# k26_baseboard_reset.net
KiCad netlist of a schematic drawn in Altium Designer
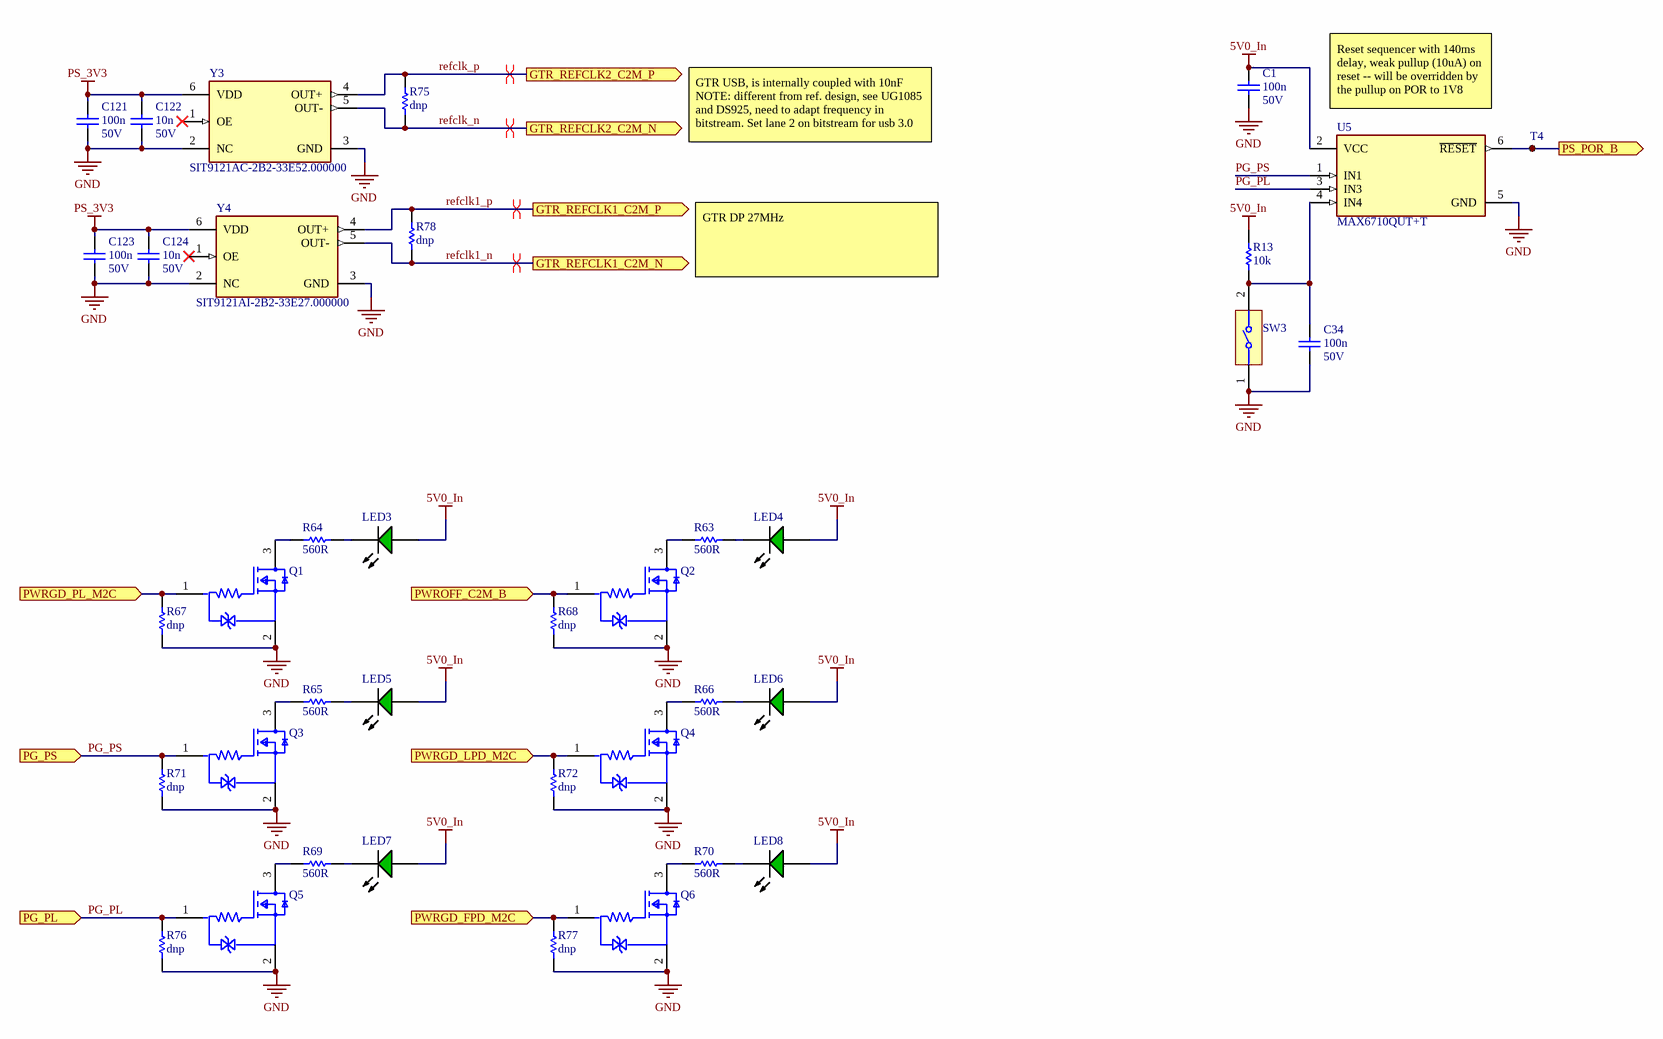
[diagram p0: k26_baseboard_reset.SchDoc]

(export (version "E")
  (design (tool "Eeschema 10.0.6"))
  (components
    (comp (ref "C1")
      (value "100n")
      (footprint "k26_FPGA_drone_baseboard:CAPC0402")
      (fields
        (field (name "MANUFACTURER") "Yageo")
        (field (name "MANUFACTURER PART NUMBER") "CC0402KRX5R9BB104")
        (field (name "RATED DC VOLTAGE (URDC)") "50V")
      )
      (libsource (lib "k26_FPGA_drone_baseboard") (part "cap0402"))
    )
    (comp (ref "C34")
      (value "100n")
      (footprint "k26_FPGA_drone_baseboard:CAPC0402")
      (fields
        (field (name "MANUFACTURER") "Yageo")
        (field (name "MANUFACTURER PART NUMBER") "CC0402KRX5R9BB104")
        (field (name "RATED DC VOLTAGE (URDC)") "50V")
      )
      (libsource (lib "k26_FPGA_drone_baseboard") (part "cap0402"))
    )
    (comp (ref "C121")
      (value "100n")
      (footprint "k26_FPGA_drone_baseboard:CAPC0402")
      (fields
        (field (name "MANUFACTURER") "Yageo")
        (field (name "MANUFACTURER PART NUMBER") "CC0402KRX5R9BB104")
        (field (name "RATED DC VOLTAGE (URDC)") "50V")
      )
      (libsource (lib "k26_FPGA_drone_baseboard") (part "cap0402"))
    )
    (comp (ref "C122")
      (value "10n")
      (footprint "k26_FPGA_drone_baseboard:CAPC0402")
      (fields
        (field (name "MANUFACTURER") "Samsung")
        (field (name "MANUFACTURER PART NUMBER") "CL05B103KB5NNNC")
        (field (name "RATED DC VOLTAGE (URDC)") "50V")
      )
      (libsource (lib "k26_FPGA_drone_baseboard") (part "cap0402"))
    )
    (comp (ref "C123")
      (value "100n")
      (footprint "k26_FPGA_drone_baseboard:CAPC0402")
      (fields
        (field (name "MANUFACTURER") "Yageo")
        (field (name "MANUFACTURER PART NUMBER") "CC0402KRX5R9BB104")
        (field (name "RATED DC VOLTAGE (URDC)") "50V")
      )
      (libsource (lib "k26_FPGA_drone_baseboard") (part "cap0402"))
    )
    (comp (ref "C124")
      (value "10n")
      (footprint "k26_FPGA_drone_baseboard:CAPC0402")
      (fields
        (field (name "MANUFACTURER") "Samsung")
        (field (name "MANUFACTURER PART NUMBER") "CL05B103KB5NNNC")
        (field (name "RATED DC VOLTAGE (URDC)") "50V")
      )
      (libsource (lib "k26_FPGA_drone_baseboard") (part "cap0402"))
    )
    (comp (ref "LED3")
      (value "LNJ347W83RA")
      (footprint "LED0402(1005)_L")
      (description "Green 572nm LED Indication - Discrete 1.95V 0402 (1005 Metric)")
      (fields (field (name "MANUFACTURER") "Panasonic SSG"))
      (libsource (lib "k26_FPGA_drone_baseboard") (part "CMP-00397-1"))
    )
    (comp (ref "LED4")
      (value "LNJ347W83RA")
      (footprint "LED0402(1005)_L")
      (description "Green 572nm LED Indication - Discrete 1.95V 0402 (1005 Metric)")
      (fields (field (name "MANUFACTURER") "Panasonic SSG"))
      (libsource (lib "k26_FPGA_drone_baseboard") (part "CMP-00397-1"))
    )
    (comp (ref "LED5")
      (value "LNJ347W83RA")
      (footprint "LED0402(1005)_L")
      (description "Green 572nm LED Indication - Discrete 1.95V 0402 (1005 Metric)")
      (fields (field (name "MANUFACTURER") "Panasonic SSG"))
      (libsource (lib "k26_FPGA_drone_baseboard") (part "CMP-00397-1"))
    )
    (comp (ref "LED6")
      (value "LNJ347W83RA")
      (footprint "LED0402(1005)_L")
      (description "Green 572nm LED Indication - Discrete 1.95V 0402 (1005 Metric)")
      (fields (field (name "MANUFACTURER") "Panasonic SSG"))
      (libsource (lib "k26_FPGA_drone_baseboard") (part "CMP-00397-1"))
    )
    (comp (ref "LED7")
      (value "LNJ347W83RA")
      (footprint "LED0402(1005)_L")
      (description "Green 572nm LED Indication - Discrete 1.95V 0402 (1005 Metric)")
      (fields (field (name "MANUFACTURER") "Panasonic SSG"))
      (libsource (lib "k26_FPGA_drone_baseboard") (part "CMP-00397-1"))
    )
    (comp (ref "LED8")
      (value "LNJ347W83RA")
      (footprint "LED0402(1005)_L")
      (description "Green 572nm LED Indication - Discrete 1.95V 0402 (1005 Metric)")
      (fields (field (name "MANUFACTURER") "Panasonic SSG"))
      (libsource (lib "k26_FPGA_drone_baseboard") (part "CMP-00397-1"))
    )
    (comp (ref "Q1")
      (value "RUM001L02T2CL")
      (footprint "FP-VMT3-MFG")
      (description "MOSFET N-CH 20V 0.1A VMT3")
      (fields
        (field (name "MANUFACTURER") "Rohm")
        (field (name "OCTOPART") "https://octopart.com/rum001l02t2cl-rohm-24403092")
      )
      (libsource (lib "k26_FPGA_drone_baseboard") (part "CMP-08982-000008-1"))
    )
    (comp (ref "Q2")
      (value "RUM001L02T2CL")
      (footprint "FP-VMT3-MFG")
      (description "MOSFET N-CH 20V 0.1A VMT3")
      (fields
        (field (name "MANUFACTURER") "Rohm")
        (field (name "OCTOPART") "https://octopart.com/rum001l02t2cl-rohm-24403092")
      )
      (libsource (lib "k26_FPGA_drone_baseboard") (part "CMP-08982-000008-1"))
    )
    (comp (ref "Q3")
      (value "RUM001L02T2CL")
      (footprint "FP-VMT3-MFG")
      (description "MOSFET N-CH 20V 0.1A VMT3")
      (fields
        (field (name "MANUFACTURER") "Rohm")
        (field (name "OCTOPART") "https://octopart.com/rum001l02t2cl-rohm-24403092")
      )
      (libsource (lib "k26_FPGA_drone_baseboard") (part "CMP-08982-000008-1"))
    )
    (comp (ref "Q4")
      (value "RUM001L02T2CL")
      (footprint "FP-VMT3-MFG")
      (description "MOSFET N-CH 20V 0.1A VMT3")
      (fields
        (field (name "MANUFACTURER") "Rohm")
        (field (name "OCTOPART") "https://octopart.com/rum001l02t2cl-rohm-24403092")
      )
      (libsource (lib "k26_FPGA_drone_baseboard") (part "CMP-08982-000008-1"))
    )
    (comp (ref "Q5")
      (value "RUM001L02T2CL")
      (footprint "FP-VMT3-MFG")
      (description "MOSFET N-CH 20V 0.1A VMT3")
      (fields
        (field (name "MANUFACTURER") "Rohm")
        (field (name "OCTOPART") "https://octopart.com/rum001l02t2cl-rohm-24403092")
      )
      (libsource (lib "k26_FPGA_drone_baseboard") (part "CMP-08982-000008-1"))
    )
    (comp (ref "Q6")
      (value "RUM001L02T2CL")
      (footprint "FP-VMT3-MFG")
      (description "MOSFET N-CH 20V 0.1A VMT3")
      (fields
        (field (name "MANUFACTURER") "Rohm")
        (field (name "OCTOPART") "https://octopart.com/rum001l02t2cl-rohm-24403092")
      )
      (libsource (lib "k26_FPGA_drone_baseboard") (part "CMP-08982-000008-1"))
    )
    (comp (ref "R13")
      (value "10k")
      (footprint "k26_FPGA_drone_baseboard:RES0402")
      (fields
        (field (name "MANUFACTURER") "Panasonic")
        (field (name "MANUFACTURER PART NUMBER") "ERJ-2RKF1002X")
        (field (name "TOLERANCE") "1%")
      )
      (libsource (lib "k26_FPGA_drone_baseboard") (part "res0402"))
    )
    (comp (ref "R63")
      (value "560R")
      (footprint "k26_FPGA_drone_baseboard:RES0402")
      (fields
        (field (name "MANUFACTURER") "Vishay")
        (field (name "MANUFACTURER PART NUMBER") "CRCW0402560RFKED")
        (field (name "TOLERANCE") "1%")
      )
      (libsource (lib "k26_FPGA_drone_baseboard") (part "res0402"))
    )
    (comp (ref "R64")
      (value "560R")
      (footprint "k26_FPGA_drone_baseboard:RES0402")
      (fields
        (field (name "MANUFACTURER") "Vishay")
        (field (name "MANUFACTURER PART NUMBER") "CRCW0402560RFKED")
        (field (name "TOLERANCE") "1%")
      )
      (libsource (lib "k26_FPGA_drone_baseboard") (part "res0402"))
    )
    (comp (ref "R65")
      (value "560R")
      (footprint "k26_FPGA_drone_baseboard:RES0402")
      (fields
        (field (name "MANUFACTURER") "Vishay")
        (field (name "MANUFACTURER PART NUMBER") "CRCW0402560RFKED")
        (field (name "TOLERANCE") "1%")
      )
      (libsource (lib "k26_FPGA_drone_baseboard") (part "res0402"))
    )
    (comp (ref "R66")
      (value "560R")
      (footprint "k26_FPGA_drone_baseboard:RES0402")
      (fields
        (field (name "MANUFACTURER") "Vishay")
        (field (name "MANUFACTURER PART NUMBER") "CRCW0402560RFKED")
        (field (name "TOLERANCE") "1%")
      )
      (libsource (lib "k26_FPGA_drone_baseboard") (part "res0402"))
    )
    (comp (ref "R67")
      (value "dnp")
      (footprint "k26_FPGA_drone_baseboard:RES0402")
      (fields
        (field (name "MANUFACTURER") "Panasonic")
        (field (name "MANUFACTURER PART NUMBER") "ERJ-2RKF4990X")
        (field (name "TOLERANCE") "1%")
      )
      (libsource (lib "k26_FPGA_drone_baseboard") (part "res0402"))
    )
    (comp (ref "R68")
      (value "dnp")
      (footprint "k26_FPGA_drone_baseboard:RES0402")
      (fields
        (field (name "MANUFACTURER") "Panasonic")
        (field (name "MANUFACTURER PART NUMBER") "ERJ-2RKF4990X")
        (field (name "TOLERANCE") "1%")
      )
      (libsource (lib "k26_FPGA_drone_baseboard") (part "res0402"))
    )
    (comp (ref "R69")
      (value "560R")
      (footprint "k26_FPGA_drone_baseboard:RES0402")
      (fields
        (field (name "MANUFACTURER") "Vishay")
        (field (name "MANUFACTURER PART NUMBER") "CRCW0402560RFKED")
        (field (name "TOLERANCE") "1%")
      )
      (libsource (lib "k26_FPGA_drone_baseboard") (part "res0402"))
    )
    (comp (ref "R70")
      (value "560R")
      (footprint "k26_FPGA_drone_baseboard:RES0402")
      (fields
        (field (name "MANUFACTURER") "Vishay")
        (field (name "MANUFACTURER PART NUMBER") "CRCW0402560RFKED")
        (field (name "TOLERANCE") "1%")
      )
      (libsource (lib "k26_FPGA_drone_baseboard") (part "res0402"))
    )
    (comp (ref "R71")
      (value "dnp")
      (footprint "k26_FPGA_drone_baseboard:RES0402")
      (fields
        (field (name "MANUFACTURER") "Panasonic")
        (field (name "MANUFACTURER PART NUMBER") "ERJ-2RKF4990X")
        (field (name "TOLERANCE") "1%")
      )
      (libsource (lib "k26_FPGA_drone_baseboard") (part "res0402"))
    )
    (comp (ref "R72")
      (value "dnp")
      (footprint "k26_FPGA_drone_baseboard:RES0402")
      (fields
        (field (name "MANUFACTURER") "Panasonic")
        (field (name "MANUFACTURER PART NUMBER") "ERJ-2RKF4990X")
        (field (name "TOLERANCE") "1%")
      )
      (libsource (lib "k26_FPGA_drone_baseboard") (part "res0402"))
    )
    (comp (ref "R75")
      (value "dnp")
      (footprint "k26_FPGA_drone_baseboard:RES0402")
      (fields
        (field (name "MANUFACTURER") "Panasonic")
        (field (name "MANUFACTURER PART NUMBER") "ERJ-2RKF4990X")
        (field (name "TOLERANCE") "1%")
      )
      (libsource (lib "k26_FPGA_drone_baseboard") (part "res0402"))
    )
    (comp (ref "R76")
      (value "dnp")
      (footprint "k26_FPGA_drone_baseboard:RES0402")
      (fields
        (field (name "MANUFACTURER") "Panasonic")
        (field (name "MANUFACTURER PART NUMBER") "ERJ-2RKF4990X")
        (field (name "TOLERANCE") "1%")
      )
      (libsource (lib "k26_FPGA_drone_baseboard") (part "res0402"))
    )
    (comp (ref "R77")
      (value "dnp")
      (footprint "k26_FPGA_drone_baseboard:RES0402")
      (fields
        (field (name "MANUFACTURER") "Panasonic")
        (field (name "MANUFACTURER PART NUMBER") "ERJ-2RKF4990X")
        (field (name "TOLERANCE") "1%")
      )
      (libsource (lib "k26_FPGA_drone_baseboard") (part "res0402"))
    )
    (comp (ref "R78")
      (value "dnp")
      (footprint "k26_FPGA_drone_baseboard:RES0402")
      (fields
        (field (name "MANUFACTURER") "Panasonic")
        (field (name "MANUFACTURER PART NUMBER") "ERJ-2RKF4990X")
        (field (name "TOLERANCE") "1%")
      )
      (libsource (lib "k26_FPGA_drone_baseboard") (part "res0402"))
    )
    (comp (ref "SW3")
      (value "KSS241GLFS")
      (footprint "KSS241GLFS")
      (description "SWITCH TACTILE SPST-NO 0.05A 50V")
      (fields (field (name "MANUFACTURER") "C&K Components"))
      (libsource (lib "k26_FPGA_drone_baseboard") (part "Push Button"))
    )
    (comp (ref "T4")
      (value "~")
      (footprint "Pad-1mm")
      (description "1mm SMT Test Pad")
      (libsource (lib "k26_FPGA_drone_baseboard") (part "Test Pad"))
    )
    (comp (ref "U5")
      (value "MAX6710QUT+T")
      (footprint "FP-U6-1-MFG")
      (description "IC SUPERVISOR 4 CHANNEL SOT23-6")
      (libsource (lib "k26_FPGA_drone_baseboard") (part "89106dfa36ac63dd32f4bf0b7805f26"))
    )
    (comp (ref "Y3")
      (value "SIT9121AC-2B2-33E52.000000")
      (footprint "FP-SiT9121-B-MFG")
      (description "MEMS OSC XO 52.0000MHZ LVDS SMD")
      (fields
        (field (name "MANUFACTURER") "SiTime")
        (field (name "MANUFACTURER PART NUMBER") "SIT9121AC-2B2-33E100.000000")
      )
      (libsource (lib "k26_FPGA_drone_baseboard") (part "CMP-25159-261142-1"))
    )
    (comp (ref "Y4")
      (value "SIT9121AI-2B2-33E27.000000")
      (footprint "FP-SiT9121-B-MFG")
      (description "MEMS OSC XO 52.0000MHZ LVDS SMD")
      (fields
        (field (name "MANUFACTURER") "SiTime")
        (field (name "MANUFACTURER PART NUMBER") "SIT9121AC-2B2-33E100.000000")
      )
      (libsource (lib "k26_FPGA_drone_baseboard") (part "CMP-25159-261142-1"))
    )
  )
  (nets
    (net (code "1") (name "/PG_PL") (class "Default")
      (node (ref "Q5") (pin "1") (pinfunction "Gate_1") (pintype "passive"))
      (node (ref "R76") (pin "2") (pinfunction "2_2") (pintype "passive"))
      (node (ref "U5") (pin "3") (pinfunction "IN3_3") (pintype "input"))
    )
    (net (code "2") (name "/PG_PS") (class "Default")
      (node (ref "Q3") (pin "1") (pinfunction "Gate_1") (pintype "passive"))
      (node (ref "R71") (pin "2") (pinfunction "2_2") (pintype "passive"))
      (node (ref "U5") (pin "1") (pinfunction "IN1_1") (pintype "input"))
    )
    (net (code "3") (name "/PS_POR_B") (class "Default")
      (node (ref "T4") (pin "1") (pinfunction "1_1") (pintype "passive"))
      (node (ref "U5") (pin "6") (pinfunction "~{RESET}_6") (pintype "output"))
    )
    (net (code "4") (name "/PWRGD_FPD_M2C") (class "Default")
      (node (ref "Q6") (pin "1") (pinfunction "Gate_1") (pintype "passive"))
      (node (ref "R77") (pin "2") (pinfunction "2_2") (pintype "passive"))
    )
    (net (code "5") (name "/PWRGD_LPD_M2C") (class "Default")
      (node (ref "Q4") (pin "1") (pinfunction "Gate_1") (pintype "passive"))
      (node (ref "R72") (pin "2") (pinfunction "2_2") (pintype "passive"))
    )
    (net (code "6") (name "/PWRGD_PL_M2C") (class "Default")
      (node (ref "Q1") (pin "1") (pinfunction "Gate_1") (pintype "passive"))
      (node (ref "R67") (pin "2") (pinfunction "2_2") (pintype "passive"))
    )
    (net (code "7") (name "/PWROFF_C2M_B") (class "Default")
      (node (ref "Q2") (pin "1") (pinfunction "Gate_1") (pintype "passive"))
      (node (ref "R68") (pin "2") (pinfunction "2_2") (pintype "passive"))
    )
    (net (code "8") (name "/refclk1_n") (class "Default")
      (node (ref "R78") (pin "1") (pinfunction "1_1") (pintype "passive"))
      (node (ref "Y4") (pin "5") (pinfunction "OUT-_5") (pintype "output"))
    )
    (net (code "9") (name "/refclk1_p") (class "Default")
      (node (ref "R78") (pin "2") (pinfunction "2_2") (pintype "passive"))
      (node (ref "Y4") (pin "4") (pinfunction "OUT+_4") (pintype "output"))
    )
    (net (code "10") (name "/refclk_n") (class "Default")
      (node (ref "R75") (pin "1") (pinfunction "1_1") (pintype "passive"))
      (node (ref "Y3") (pin "5") (pinfunction "OUT-_5") (pintype "output"))
    )
    (net (code "11") (name "/refclk_p") (class "Default")
      (node (ref "R75") (pin "2") (pinfunction "2_2") (pintype "passive"))
      (node (ref "Y3") (pin "4") (pinfunction "OUT+_4") (pintype "output"))
    )
    (net (code "12") (name "5V0_In") (class "Default")
      (node (ref "C1") (pin "2") (pinfunction "2_2") (pintype "passive"))
      (node (ref "LED3") (pin "1") (pinfunction "A_1") (pintype "passive"))
      (node (ref "LED4") (pin "1") (pinfunction "A_1") (pintype "passive"))
      (node (ref "LED5") (pin "1") (pinfunction "A_1") (pintype "passive"))
      (node (ref "LED6") (pin "1") (pinfunction "A_1") (pintype "passive"))
      (node (ref "LED7") (pin "1") (pinfunction "A_1") (pintype "passive"))
      (node (ref "LED8") (pin "1") (pinfunction "A_1") (pintype "passive"))
      (node (ref "R13") (pin "2") (pinfunction "2_2") (pintype "passive"))
      (node (ref "U5") (pin "2") (pinfunction "VCC_2") (pintype "power_in"))
    )
    (net (code "13") (name "GND") (class "Default")
      (node (ref "C1") (pin "1") (pinfunction "1_1") (pintype "passive"))
      (node (ref "C121") (pin "1") (pinfunction "1_1") (pintype "passive"))
      (node (ref "C122") (pin "1") (pinfunction "1_1") (pintype "passive"))
      (node (ref "C123") (pin "1") (pinfunction "1_1") (pintype "passive"))
      (node (ref "C124") (pin "1") (pinfunction "1_1") (pintype "passive"))
      (node (ref "C34") (pin "1") (pinfunction "1_1") (pintype "passive"))
      (node (ref "Q1") (pin "2") (pinfunction "Source_2") (pintype "passive"))
      (node (ref "Q2") (pin "2") (pinfunction "Source_2") (pintype "passive"))
      (node (ref "Q3") (pin "2") (pinfunction "Source_2") (pintype "passive"))
      (node (ref "Q4") (pin "2") (pinfunction "Source_2") (pintype "passive"))
      (node (ref "Q5") (pin "2") (pinfunction "Source_2") (pintype "passive"))
      (node (ref "Q6") (pin "2") (pinfunction "Source_2") (pintype "passive"))
      (node (ref "R67") (pin "1") (pinfunction "1_1") (pintype "passive"))
      (node (ref "R68") (pin "1") (pinfunction "1_1") (pintype "passive"))
      (node (ref "R71") (pin "1") (pinfunction "1_1") (pintype "passive"))
      (node (ref "R72") (pin "1") (pinfunction "1_1") (pintype "passive"))
      (node (ref "R76") (pin "1") (pinfunction "1_1") (pintype "passive"))
      (node (ref "R77") (pin "1") (pinfunction "1_1") (pintype "passive"))
      (node (ref "SW3") (pin "1") (pinfunction "T1_1") (pintype "passive"))
      (node (ref "U5") (pin "5") (pinfunction "GND_5") (pintype "power_in"))
      (node (ref "Y3") (pin "2") (pinfunction "NC_2") (pintype "passive"))
      (node (ref "Y3") (pin "3") (pinfunction "GND_3") (pintype "power_in"))
      (node (ref "Y4") (pin "2") (pinfunction "NC_2") (pintype "passive"))
      (node (ref "Y4") (pin "3") (pinfunction "GND_3") (pintype "power_in"))
    )
    (net (code "14") (name "Net-(LED3-K)") (class "Default")
      (node (ref "LED3") (pin "2") (pinfunction "K_2") (pintype "passive"))
      (node (ref "R64") (pin "2") (pinfunction "2_2") (pintype "passive"))
    )
    (net (code "15") (name "Net-(LED4-K)") (class "Default")
      (node (ref "LED4") (pin "2") (pinfunction "K_2") (pintype "passive"))
      (node (ref "R63") (pin "2") (pinfunction "2_2") (pintype "passive"))
    )
    (net (code "16") (name "Net-(LED5-K)") (class "Default")
      (node (ref "LED5") (pin "2") (pinfunction "K_2") (pintype "passive"))
      (node (ref "R65") (pin "2") (pinfunction "2_2") (pintype "passive"))
    )
    (net (code "17") (name "Net-(LED6-K)") (class "Default")
      (node (ref "LED6") (pin "2") (pinfunction "K_2") (pintype "passive"))
      (node (ref "R66") (pin "2") (pinfunction "2_2") (pintype "passive"))
    )
    (net (code "18") (name "Net-(LED7-K)") (class "Default")
      (node (ref "LED7") (pin "2") (pinfunction "K_2") (pintype "passive"))
      (node (ref "R69") (pin "2") (pinfunction "2_2") (pintype "passive"))
    )
    (net (code "19") (name "Net-(LED8-K)") (class "Default")
      (node (ref "LED8") (pin "2") (pinfunction "K_2") (pintype "passive"))
      (node (ref "R70") (pin "2") (pinfunction "2_2") (pintype "passive"))
    )
    (net (code "20") (name "Net-(Q1-Drain)") (class "Default")
      (node (ref "Q1") (pin "3") (pinfunction "Drain_3") (pintype "passive"))
      (node (ref "R64") (pin "1") (pinfunction "1_1") (pintype "passive"))
    )
    (net (code "21") (name "Net-(Q2-Drain)") (class "Default")
      (node (ref "Q2") (pin "3") (pinfunction "Drain_3") (pintype "passive"))
      (node (ref "R63") (pin "1") (pinfunction "1_1") (pintype "passive"))
    )
    (net (code "22") (name "Net-(Q3-Drain)") (class "Default")
      (node (ref "Q3") (pin "3") (pinfunction "Drain_3") (pintype "passive"))
      (node (ref "R65") (pin "1") (pinfunction "1_1") (pintype "passive"))
    )
    (net (code "23") (name "Net-(Q4-Drain)") (class "Default")
      (node (ref "Q4") (pin "3") (pinfunction "Drain_3") (pintype "passive"))
      (node (ref "R66") (pin "1") (pinfunction "1_1") (pintype "passive"))
    )
    (net (code "24") (name "Net-(Q5-Drain)") (class "Default")
      (node (ref "Q5") (pin "3") (pinfunction "Drain_3") (pintype "passive"))
      (node (ref "R69") (pin "1") (pinfunction "1_1") (pintype "passive"))
    )
    (net (code "25") (name "Net-(Q6-Drain)") (class "Default")
      (node (ref "Q6") (pin "3") (pinfunction "Drain_3") (pintype "passive"))
      (node (ref "R70") (pin "1") (pinfunction "1_1") (pintype "passive"))
    )
    (net (code "26") (name "Net-(SW3-T2)") (class "Default")
      (node (ref "C34") (pin "2") (pinfunction "2_2") (pintype "passive"))
      (node (ref "R13") (pin "1") (pinfunction "1_1") (pintype "passive"))
      (node (ref "SW3") (pin "2") (pinfunction "T2_2") (pintype "passive"))
      (node (ref "U5") (pin "4") (pinfunction "IN4_4") (pintype "input"))
    )
    (net (code "27") (name "PS_3V3") (class "Default")
      (node (ref "C121") (pin "2") (pinfunction "2_2") (pintype "passive"))
      (node (ref "C122") (pin "2") (pinfunction "2_2") (pintype "passive"))
      (node (ref "C123") (pin "2") (pinfunction "2_2") (pintype "passive"))
      (node (ref "C124") (pin "2") (pinfunction "2_2") (pintype "passive"))
      (node (ref "Y3") (pin "6") (pinfunction "VDD_6") (pintype "power_in"))
      (node (ref "Y4") (pin "6") (pinfunction "VDD_6") (pintype "power_in"))
    )
    (net (code "28") (name "unconnected-(Y3-OE-Pad1)") (class "Default")
      (node (ref "Y3") (pin "1") (pinfunction "OE_1") (pintype "input+no_connect"))
    )
    (net (code "29") (name "unconnected-(Y4-OE-Pad1)") (class "Default")
      (node (ref "Y4") (pin "1") (pinfunction "OE_1") (pintype "input+no_connect"))
    )
  )
)
